# PCB_DYBoard_Bandmaster_V2_SCH2.net
KiCad netlist of a schematic drawn in Altium Designer
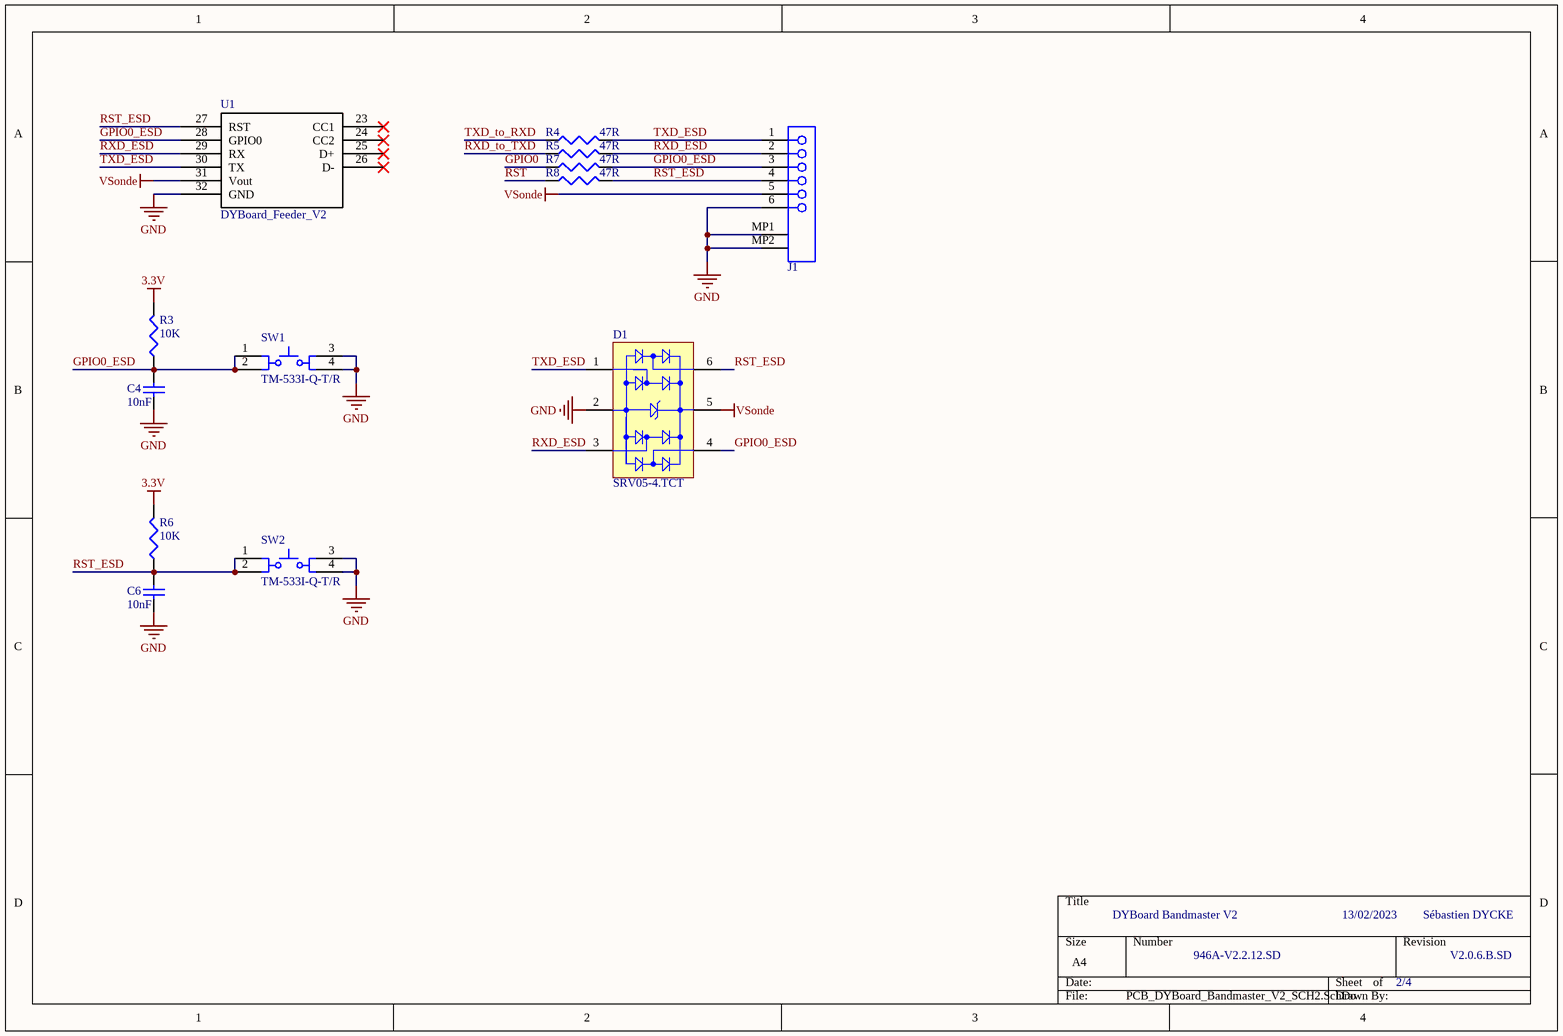
[diagram p0: PCB_DYBoard_Bandmaster_V2_SCH2.SchDoc]

(export (version "E")
  (design (tool "Eeschema 10.0.6"))
  (components
    (comp (ref "C4")
      (value "10nF")
      (footprint "1608[0603]")
      (description "Capacitor (Semiconductor SIM Model)")
      (fields (field (name "Comment") "Cap Semi") (field (name "PUBLISHER") "Altium Limited"))
      (libsource (lib "Miscellaneous Devices") (part "Cap Semi"))
    )
    (comp (ref "C6")
      (value "10nF")
      (footprint "1608[0603]")
      (description "Capacitor (Semiconductor SIM Model)")
      (fields (field (name "Comment") "Cap Semi") (field (name "PUBLISHER") "Altium Limited"))
      (libsource (lib "Miscellaneous Devices") (part "Cap Semi"))
    )
    (comp (ref "D1")
      (value "SRV05-4.TCT")
      (footprint "SMTC-SOT23-6_V")
      (fields (field (name "MANUFACTURER") "Semtech"))
      (libsource (lib "Altium Content Vault") (part "STM-USB_DVI_HDMIULC6-4SC6X-SOT23-6L"))
    )
    (comp (ref "J1")
      (value "SEB_MOLeX_6p")
      (footprint "SEB_MOLeX_6p")
      (libsource (lib "AQ7538-08UTG") (part "SEB_MOLeX_6p"))
    )
    (comp (ref "R3")
      (value "10K")
      (footprint "J1-0603")
      (description "Resistor")
      (fields (field (name "Comment") "Res3") (field (name "PUBLISHER") "Altium Limited"))
      (libsource (lib "Miscellaneous Devices") (part "Res3"))
    )
    (comp (ref "R4")
      (value "47R")
      (footprint "J1-0603")
      (description "Resistor")
      (fields (field (name "Comment") "Res3") (field (name "PUBLISHER") "Altium Limited"))
      (libsource (lib "Miscellaneous Devices") (part "Res3"))
    )
    (comp (ref "R5")
      (value "47R")
      (footprint "J1-0603")
      (description "Resistor")
      (fields (field (name "Comment") "Res3") (field (name "PUBLISHER") "Altium Limited"))
      (libsource (lib "Miscellaneous Devices") (part "Res3"))
    )
    (comp (ref "R6")
      (value "10K")
      (footprint "J1-0603")
      (description "Resistor")
      (fields (field (name "Comment") "Res3") (field (name "PUBLISHER") "Altium Limited"))
      (libsource (lib "Miscellaneous Devices") (part "Res3"))
    )
    (comp (ref "R7")
      (value "47R")
      (footprint "J1-0603")
      (description "Resistor")
      (fields (field (name "Comment") "Res3") (field (name "PUBLISHER") "Altium Limited"))
      (libsource (lib "Miscellaneous Devices") (part "Res3"))
    )
    (comp (ref "R8")
      (value "47R")
      (footprint "J1-0603")
      (description "Resistor")
      (fields (field (name "Comment") "Res3") (field (name "PUBLISHER") "Altium Limited"))
      (libsource (lib "Miscellaneous Devices") (part "Res3"))
    )
    (comp (ref "SW1")
      (value "TM-533I-Q-T/R")
      (footprint "MULT-TM-533I-Q_V")
      (description "TACT Switch, SPNO, -25 to 70 degC, 4-Pin SMD, RoHS, Tape and Reel")
      (libsource (lib "Altium Content Vault") (part "SW-SPST-NO-4"))
    )
    (comp (ref "SW2")
      (value "TM-533I-Q-T/R")
      (footprint "MULT-TM-533I-Q_V")
      (description "TACT Switch, SPNO, -25 to 70 degC, 4-Pin SMD, RoHS, Tape and Reel")
      (libsource (lib "Altium Content Vault") (part "SW-SPST-NO-4"))
    )
    (comp (ref "U1")
      (value "DYBoard_Feeder_V2")
      (footprint "DYBoard_Feeder_V2")
      (libsource (lib "Lib_Altium_Sebastien_DYCKE") (part "DYBoard_Feeder_V2"))
    )
  )
  (nets
    (net (code "1") (name "/GPIO0") (class "Default")
      (node (ref "R7") (pin "1") (pinfunction "1_1") (pintype "passive"))
    )
    (net (code "2") (name "/GPIO0_ESD") (class "Default")
      (node (ref "C4") (pin "2") (pinfunction "2_2") (pintype "passive"))
      (node (ref "D1") (pin "4") (pinfunction "I/O_3_4") (pintype "passive"))
      (node (ref "J1") (pin "3") (pinfunction "3_3") (pintype "passive"))
      (node (ref "R3") (pin "1") (pinfunction "1_1") (pintype "passive"))
      (node (ref "R7") (pin "2") (pinfunction "2_2") (pintype "passive"))
      (node (ref "SW1") (pin "1") (pinfunction "1_1") (pintype "passive"))
      (node (ref "SW1") (pin "2") (pinfunction "2_2") (pintype "passive"))
      (node (ref "U1") (pin "28") (pinfunction "GPIO0_28") (pintype "passive"))
    )
    (net (code "3") (name "/RST") (class "Default")
      (node (ref "R8") (pin "1") (pinfunction "1_1") (pintype "passive"))
    )
    (net (code "4") (name "/RST_ESD") (class "Default")
      (node (ref "C6") (pin "2") (pinfunction "2_2") (pintype "passive"))
      (node (ref "D1") (pin "6") (pinfunction "I/O_4_6") (pintype "passive"))
      (node (ref "J1") (pin "4") (pinfunction "4_4") (pintype "passive"))
      (node (ref "R6") (pin "1") (pinfunction "1_1") (pintype "passive"))
      (node (ref "R8") (pin "2") (pinfunction "2_2") (pintype "passive"))
      (node (ref "SW2") (pin "1") (pinfunction "1_1") (pintype "passive"))
      (node (ref "SW2") (pin "2") (pinfunction "2_2") (pintype "passive"))
      (node (ref "U1") (pin "27") (pinfunction "RST_27") (pintype "passive"))
    )
    (net (code "5") (name "/RXD_ESD") (class "Default")
      (node (ref "D1") (pin "3") (pinfunction "I/O_2_3") (pintype "passive"))
      (node (ref "J1") (pin "2") (pinfunction "2_2") (pintype "passive"))
      (node (ref "R5") (pin "2") (pinfunction "2_2") (pintype "passive"))
      (node (ref "U1") (pin "29") (pinfunction "RX_29") (pintype "passive"))
    )
    (net (code "6") (name "/RXD_to_TXD") (class "Default")
      (node (ref "R5") (pin "1") (pinfunction "1_1") (pintype "passive"))
    )
    (net (code "7") (name "/TXD_ESD") (class "Default")
      (node (ref "D1") (pin "1") (pinfunction "I/O_1_1") (pintype "passive"))
      (node (ref "J1") (pin "1") (pinfunction "1_1") (pintype "passive"))
      (node (ref "R4") (pin "2") (pinfunction "2_2") (pintype "passive"))
      (node (ref "U1") (pin "30") (pinfunction "TX_30") (pintype "passive"))
    )
    (net (code "8") (name "/TXD_to_RXD") (class "Default")
      (node (ref "R4") (pin "1") (pinfunction "1_1") (pintype "passive"))
    )
    (net (code "9") (name "3.3V") (class "Default")
      (node (ref "R3") (pin "2") (pinfunction "2_2") (pintype "passive"))
      (node (ref "R6") (pin "2") (pinfunction "2_2") (pintype "passive"))
    )
    (net (code "10") (name "GND") (class "Default")
      (node (ref "C4") (pin "1") (pinfunction "1_1") (pintype "passive"))
      (node (ref "C6") (pin "1") (pinfunction "1_1") (pintype "passive"))
      (node (ref "D1") (pin "2") (pinfunction "GND_2") (pintype "passive"))
      (node (ref "J1") (pin "6") (pinfunction "6_6") (pintype "passive"))
      (node (ref "J1") (pin "MP1") (pinfunction "MP1_MP1") (pintype "passive"))
      (node (ref "J1") (pin "MP2") (pinfunction "MP2_MP2") (pintype "passive"))
      (node (ref "SW1") (pin "3") (pinfunction "3_3") (pintype "passive"))
      (node (ref "SW1") (pin "4") (pinfunction "4_4") (pintype "passive"))
      (node (ref "SW2") (pin "3") (pinfunction "3_3") (pintype "passive"))
      (node (ref "SW2") (pin "4") (pinfunction "4_4") (pintype "passive"))
      (node (ref "U1") (pin "32") (pinfunction "GND_32") (pintype "passive"))
    )
    (net (code "11") (name "VSonde") (class "Default")
      (node (ref "D1") (pin "5") (pinfunction "VBUS_5") (pintype "passive"))
      (node (ref "J1") (pin "5") (pinfunction "5_5") (pintype "passive"))
      (node (ref "U1") (pin "31") (pinfunction "Vout_31") (pintype "passive"))
    )
    (net (code "12") (name "unconnected-(U1-CC1-Pad23)") (class "Default")
      (node (ref "U1") (pin "23") (pinfunction "CC1_23") (pintype "passive+no_connect"))
    )
    (net (code "13") (name "unconnected-(U1-CC2-Pad24)") (class "Default")
      (node (ref "U1") (pin "24") (pinfunction "CC2_24") (pintype "passive+no_connect"))
    )
    (net (code "14") (name "unconnected-(U1-D+-Pad25)") (class "Default")
      (node (ref "U1") (pin "25") (pinfunction "D+_25") (pintype "passive+no_connect"))
    )
    (net (code "15") (name "unconnected-(U1-D--Pad26)") (class "Default")
      (node (ref "U1") (pin "26") (pinfunction "D-_26") (pintype "passive+no_connect"))
    )
  )
)
